# lb_single-sided_uno_v2.net
KiCad netlist of a schematic drawn in EAGLE
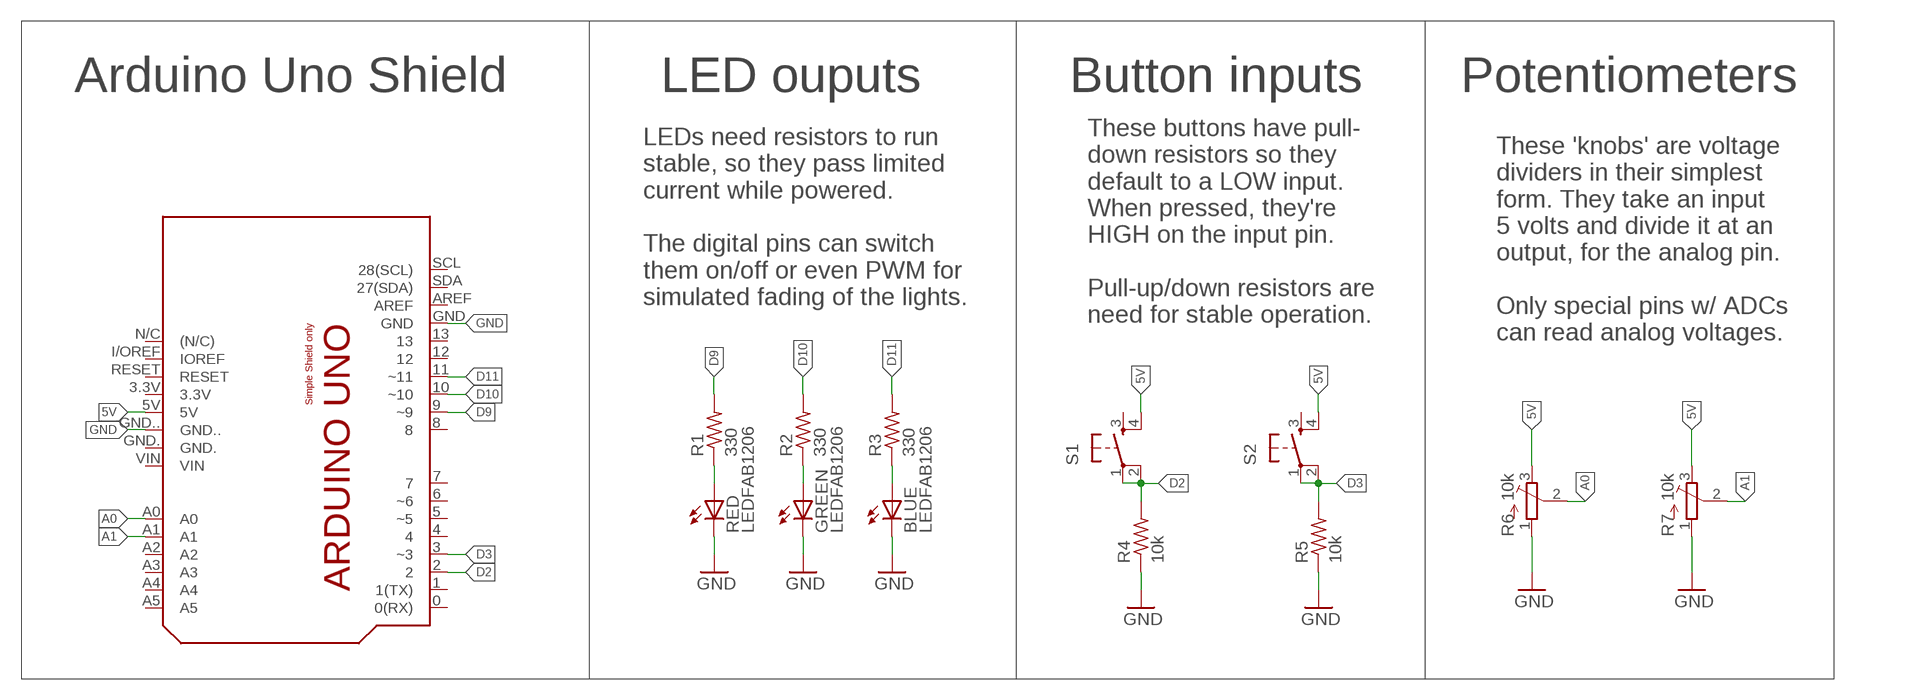
[diagram p0: schematic, sheet 1]

(export (version "E")
  (design (tool "Eeschema 10.0.6"))
  (components
    (comp (ref "BLUE")
      (value "LEDFAB1206")
      (footprint "eagle-import:LED1206FAB")
      (libsource (lib "eagle-import") (part "LEDFAB1206"))
    )
    (comp (ref "GREEN")
      (value "LEDFAB1206")
      (footprint "eagle-import:LED1206FAB")
      (libsource (lib "eagle-import") (part "LEDFAB1206"))
    )
    (comp (ref "PCB1")
      (value "ARDUINO_UNO_V2")
      (footprint "eagle-import:ARDUINO_UNO_V2")
      (libsource (lib "eagle-import") (part "ARDUINO_UNO_V2"))
    )
    (comp (ref "R1")
      (value "330")
      (footprint "eagle-import:R1206FAB")
      (libsource (lib "eagle-import") (part "RES-US1206FAB"))
    )
    (comp (ref "R2")
      (value "330")
      (footprint "eagle-import:R1206FAB")
      (libsource (lib "eagle-import") (part "RES-US1206FAB"))
    )
    (comp (ref "R3")
      (value "330")
      (footprint "eagle-import:R1206FAB")
      (libsource (lib "eagle-import") (part "RES-US1206FAB"))
    )
    (comp (ref "R4")
      (value "10k")
      (footprint "eagle-import:R1206FAB")
      (libsource (lib "eagle-import") (part "RES-US1206FAB"))
    )
    (comp (ref "R5")
      (value "10k")
      (footprint "eagle-import:R1206FAB")
      (libsource (lib "eagle-import") (part "RES-US1206FAB"))
    )
    (comp (ref "R6")
      (value "10k")
      (footprint "eagle-import:TC33X")
      (libsource (lib "eagle-import") (part "TRIMPOTTC33X"))
    )
    (comp (ref "R7")
      (value "10k")
      (footprint "eagle-import:TC33X")
      (libsource (lib "eagle-import") (part "TRIMPOTTC33X"))
    )
    (comp (ref "RED")
      (value "LEDFAB1206")
      (footprint "eagle-import:LED1206FAB")
      (libsource (lib "eagle-import") (part "LEDFAB1206"))
    )
    (comp (ref "S1")
      (value "6MM_SWITCH6MM_SWITCH")
      (footprint "eagle-import:6MM_SWITCH")
      (libsource (lib "eagle-import") (part "6MM_SWITCH6MM_SWITCH"))
    )
    (comp (ref "S2")
      (value "6MM_SWITCH6MM_SWITCH")
      (footprint "eagle-import:6MM_SWITCH")
      (libsource (lib "eagle-import") (part "6MM_SWITCH6MM_SWITCH"))
    )
  )
  (nets
    (net (code "1") (name "5V") (class "Default")
      (node (ref "PCB1") (pin "5V") (pinfunction "5V_5V") (pintype "bidirectional"))
      (node (ref "R6") (pin "3") (pinfunction "E_3") (pintype "passive"))
      (node (ref "R7") (pin "3") (pinfunction "E_3") (pintype "passive"))
      (node (ref "S1") (pin "4") (pinfunction "S1_4") (pintype "passive"))
      (node (ref "S2") (pin "4") (pinfunction "S1_4") (pintype "passive"))
    )
    (net (code "2") (name "A0") (class "Default")
      (node (ref "PCB1") (pin "A0") (pinfunction "A0_A0") (pintype "bidirectional"))
      (node (ref "R6") (pin "2") (pinfunction "S_2") (pintype "passive"))
    )
    (net (code "3") (name "A1") (class "Default")
      (node (ref "PCB1") (pin "A1") (pinfunction "A1_A1") (pintype "bidirectional"))
      (node (ref "R7") (pin "2") (pinfunction "S_2") (pintype "passive"))
    )
    (net (code "4") (name "D2") (class "Default")
      (node (ref "PCB1") (pin "2") (pinfunction "2_2") (pintype "bidirectional"))
      (node (ref "R4") (pin "2") (pinfunction "2_2") (pintype "passive"))
      (node (ref "S1") (pin "1") (pinfunction "P_1") (pintype "passive"))
      (node (ref "S1") (pin "2") (pinfunction "P1_2") (pintype "passive"))
    )
    (net (code "5") (name "D3") (class "Default")
      (node (ref "PCB1") (pin "3") (pinfunction "~{3}_3") (pintype "bidirectional"))
      (node (ref "R5") (pin "2") (pinfunction "2_2") (pintype "passive"))
      (node (ref "S2") (pin "1") (pinfunction "P_1") (pintype "passive"))
      (node (ref "S2") (pin "2") (pinfunction "P1_2") (pintype "passive"))
    )
    (net (code "6") (name "D9") (class "Default")
      (node (ref "PCB1") (pin "9") (pinfunction "~{9}_9") (pintype "bidirectional"))
      (node (ref "R1") (pin "2") (pinfunction "2_2") (pintype "passive"))
    )
    (net (code "7") (name "D10") (class "Default")
      (node (ref "PCB1") (pin "10") (pinfunction "~{10}_10") (pintype "bidirectional"))
      (node (ref "R2") (pin "2") (pinfunction "2_2") (pintype "passive"))
    )
    (net (code "8") (name "D11") (class "Default")
      (node (ref "PCB1") (pin "11") (pinfunction "~{11}_11") (pintype "bidirectional"))
      (node (ref "R3") (pin "2") (pinfunction "2_2") (pintype "passive"))
    )
    (net (code "9") (name "GND") (class "Default")
      (node (ref "BLUE") (pin "2") (pinfunction "C_2") (pintype "passive"))
      (node (ref "GREEN") (pin "2") (pinfunction "C_2") (pintype "passive"))
      (node (ref "PCB1") (pin "GND") (pinfunction "GND_GND") (pintype "bidirectional"))
      (node (ref "PCB1") (pin "GND..") (pinfunction "GND.._GND..") (pintype "bidirectional"))
      (node (ref "R4") (pin "1") (pinfunction "1_1") (pintype "passive"))
      (node (ref "R5") (pin "1") (pinfunction "1_1") (pintype "passive"))
      (node (ref "R6") (pin "1") (pinfunction "A_1") (pintype "passive"))
      (node (ref "R7") (pin "1") (pinfunction "A_1") (pintype "passive"))
      (node (ref "RED") (pin "2") (pinfunction "C_2") (pintype "passive"))
    )
    (net (code "10") (name "Net-(BLUE-A)") (class "Default")
      (node (ref "BLUE") (pin "1") (pinfunction "A_1") (pintype "passive"))
      (node (ref "R3") (pin "1") (pinfunction "1_1") (pintype "passive"))
    )
    (net (code "11") (name "Net-(GREEN-A)") (class "Default")
      (node (ref "GREEN") (pin "1") (pinfunction "A_1") (pintype "passive"))
      (node (ref "R2") (pin "1") (pinfunction "1_1") (pintype "passive"))
    )
    (net (code "12") (name "Net-(RED-A)") (class "Default")
      (node (ref "R1") (pin "1") (pinfunction "1_1") (pintype "passive"))
      (node (ref "RED") (pin "1") (pinfunction "A_1") (pintype "passive"))
    )
    (net (code "13") (name "unconnected-(PCB1-(N{slash}C)-PadN{slash}C)") (class "Default")
      (node (ref "PCB1") (pin "N/C") (pinfunction "(N/C)_N/C") (pintype "bidirectional"))
    )
    (net (code "14") (name "unconnected-(PCB1-0(RX)-Pad0)") (class "Default")
      (node (ref "PCB1") (pin "0") (pinfunction "0(RX)_0") (pintype "bidirectional"))
    )
    (net (code "15") (name "unconnected-(PCB1-1(TX)-Pad1)") (class "Default")
      (node (ref "PCB1") (pin "1") (pinfunction "1(TX)_1") (pintype "bidirectional"))
    )
    (net (code "16") (name "unconnected-(PCB1-27(SDA)-PadSDA)") (class "Default")
      (node (ref "PCB1") (pin "SDA") (pinfunction "27(SDA)_SDA") (pintype "bidirectional"))
    )
    (net (code "17") (name "unconnected-(PCB1-28(SCL)-PadSCL)") (class "Default")
      (node (ref "PCB1") (pin "SCL") (pinfunction "28(SCL)_SCL") (pintype "bidirectional"))
    )
    (net (code "18") (name "unconnected-(PCB1-IOREF-PadI{slash}OREF)") (class "Default")
      (node (ref "PCB1") (pin "I/OREF") (pinfunction "IOREF_I/OREF") (pintype "bidirectional"))
    )
    (net (code "19") (name "unconnected-(PCB1-Pad3.3V)") (class "Default")
      (node (ref "PCB1") (pin "3.3V") (pinfunction "3.3V_3.3V") (pintype "bidirectional"))
    )
    (net (code "20") (name "unconnected-(PCB1-Pad4)") (class "Default")
      (node (ref "PCB1") (pin "4") (pinfunction "4_4") (pintype "bidirectional"))
    )
    (net (code "21") (name "unconnected-(PCB1-Pad7)") (class "Default")
      (node (ref "PCB1") (pin "7") (pinfunction "7_7") (pintype "bidirectional"))
    )
    (net (code "22") (name "unconnected-(PCB1-Pad8)") (class "Default")
      (node (ref "PCB1") (pin "8") (pinfunction "8_8") (pintype "bidirectional"))
    )
    (net (code "23") (name "unconnected-(PCB1-Pad12)") (class "Default")
      (node (ref "PCB1") (pin "12") (pinfunction "12_12") (pintype "bidirectional"))
    )
    (net (code "24") (name "unconnected-(PCB1-Pad13)") (class "Default")
      (node (ref "PCB1") (pin "13") (pinfunction "13_13") (pintype "bidirectional"))
    )
    (net (code "25") (name "unconnected-(PCB1-PadA2)") (class "Default")
      (node (ref "PCB1") (pin "A2") (pinfunction "A2_A2") (pintype "bidirectional"))
    )
    (net (code "26") (name "unconnected-(PCB1-PadA3)") (class "Default")
      (node (ref "PCB1") (pin "A3") (pinfunction "A3_A3") (pintype "bidirectional"))
    )
    (net (code "27") (name "unconnected-(PCB1-PadA4)") (class "Default")
      (node (ref "PCB1") (pin "A4") (pinfunction "A4_A4") (pintype "bidirectional"))
    )
    (net (code "28") (name "unconnected-(PCB1-PadA5)") (class "Default")
      (node (ref "PCB1") (pin "A5") (pinfunction "A5_A5") (pintype "bidirectional"))
    )
    (net (code "29") (name "unconnected-(PCB1-PadAREF)") (class "Default")
      (node (ref "PCB1") (pin "AREF") (pinfunction "AREF_AREF") (pintype "bidirectional"))
    )
    (net (code "30") (name "unconnected-(PCB1-PadGND.)") (class "Default")
      (node (ref "PCB1") (pin "GND.") (pinfunction "GND._GND.") (pintype "bidirectional"))
    )
    (net (code "31") (name "unconnected-(PCB1-PadRESET)") (class "Default")
      (node (ref "PCB1") (pin "RESET") (pinfunction "RESET_RESET") (pintype "bidirectional"))
    )
    (net (code "32") (name "unconnected-(PCB1-PadVIN)") (class "Default")
      (node (ref "PCB1") (pin "VIN") (pinfunction "VIN_VIN") (pintype "bidirectional"))
    )
    (net (code "33") (name "unconnected-(PCB1-~{5}-Pad5)") (class "Default")
      (node (ref "PCB1") (pin "5") (pinfunction "~{5}_5") (pintype "bidirectional"))
    )
    (net (code "34") (name "unconnected-(PCB1-~{6}-Pad6)") (class "Default")
      (node (ref "PCB1") (pin "6") (pinfunction "~{6}_6") (pintype "bidirectional"))
    )
    (net (code "35") (name "unconnected-(S1-S-Pad3)") (class "Default")
      (node (ref "S1") (pin "3") (pinfunction "S_3") (pintype "passive"))
    )
    (net (code "36") (name "unconnected-(S2-S-Pad3)") (class "Default")
      (node (ref "S2") (pin "3") (pinfunction "S_3") (pintype "passive"))
    )
  )
)
